# Calculate_input.net
KiCad netlist of a schematic drawn in Altium Designer
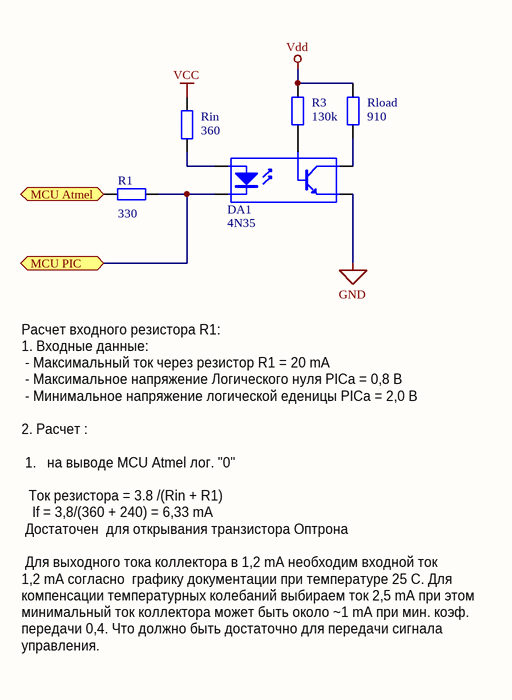
[diagram p0: Calculate input.SchDoc]

(export (version "E")
  (design (tool "Eeschema 10.0.6"))
  (components
    (comp (ref "DA1")
      (value "4N35")
      (footprint "SOP5(6)")
      (description "5 Pin Mini Flat Pack Optocoupler")
      (fields (field (name "PUBLISHER") "Altium Limited"))
      (libsource (lib "Miscellaneous Devices") (part "Optoisolator2"))
    )
    (comp (ref "R1")
      (value "330")
      (footprint "AXIAL-0.4")
      (description "Resistor")
      (fields (field (name "Comment") "Res2") (field (name "PUBLISHER") "Altium Limited"))
      (libsource (lib "") (part "Res2_1"))
    )
    (comp (ref "R3")
      (value "130k")
      (footprint "AXIAL-0.4")
      (description "Resistor")
      (fields (field (name "Comment") "Res2") (field (name "PUBLISHER") "Altium Limited"))
      (libsource (lib "Miscellaneous Devices") (part "Res2"))
    )
    (comp (ref "Rin")
      (value "360")
      (footprint "AXIAL-0.4")
      (description "Resistor")
      (fields (field (name "Comment") "Res2") (field (name "PUBLISHER") "Altium Limited"))
      (libsource (lib "Miscellaneous Devices") (part "Res2"))
    )
    (comp (ref "Rload")
      (value "910")
      (footprint "AXIAL-0.4")
      (description "Resistor")
      (fields (field (name "Comment") "Res2") (field (name "PUBLISHER") "Altium Limited"))
      (libsource (lib "Miscellaneous Devices") (part "Res2"))
    )
  )
  (nets
    (net (code "1") (name "/MCU Atmel") (class "Default")
      (node (ref "R1") (pin "2") (pinfunction "2_2") (pintype "passive"))
    )
    (net (code "2") (name "/MCU PIC") (class "Default")
      (node (ref "DA1") (pin "3") (pinfunction "K_3") (pintype "passive"))
      (node (ref "R1") (pin "1") (pinfunction "1_1") (pintype "passive"))
    )
    (net (code "3") (name "GND") (class "Default")
      (node (ref "DA1") (pin "4") (pinfunction "E_4") (pintype "passive"))
    )
    (net (code "4") (name "Net-(DA1-A)") (class "Default")
      (node (ref "DA1") (pin "1") (pinfunction "A_1") (pintype "passive"))
      (node (ref "Rin") (pin "1") (pinfunction "1_1") (pintype "passive"))
    )
    (net (code "5") (name "Net-(DA1-B)") (class "Default")
      (node (ref "DA1") (pin "6") (pinfunction "B_6") (pintype "passive"))
      (node (ref "R3") (pin "1") (pinfunction "1_1") (pintype "passive"))
    )
    (net (code "6") (name "Net-(DA1-C)") (class "Default")
      (node (ref "DA1") (pin "5") (pinfunction "C_5") (pintype "passive"))
      (node (ref "Rload") (pin "1") (pinfunction "1_1") (pintype "passive"))
    )
    (net (code "7") (name "VCC") (class "Default")
      (node (ref "Rin") (pin "2") (pinfunction "2_2") (pintype "passive"))
    )
    (net (code "8") (name "Vdd") (class "Default")
      (node (ref "R3") (pin "2") (pinfunction "2_2") (pintype "passive"))
      (node (ref "Rload") (pin "2") (pinfunction "2_2") (pintype "passive"))
    )
  )
)
